# 09-Switch_Power_Filters.net
KiCad netlist of a schematic drawn in Altium Designer
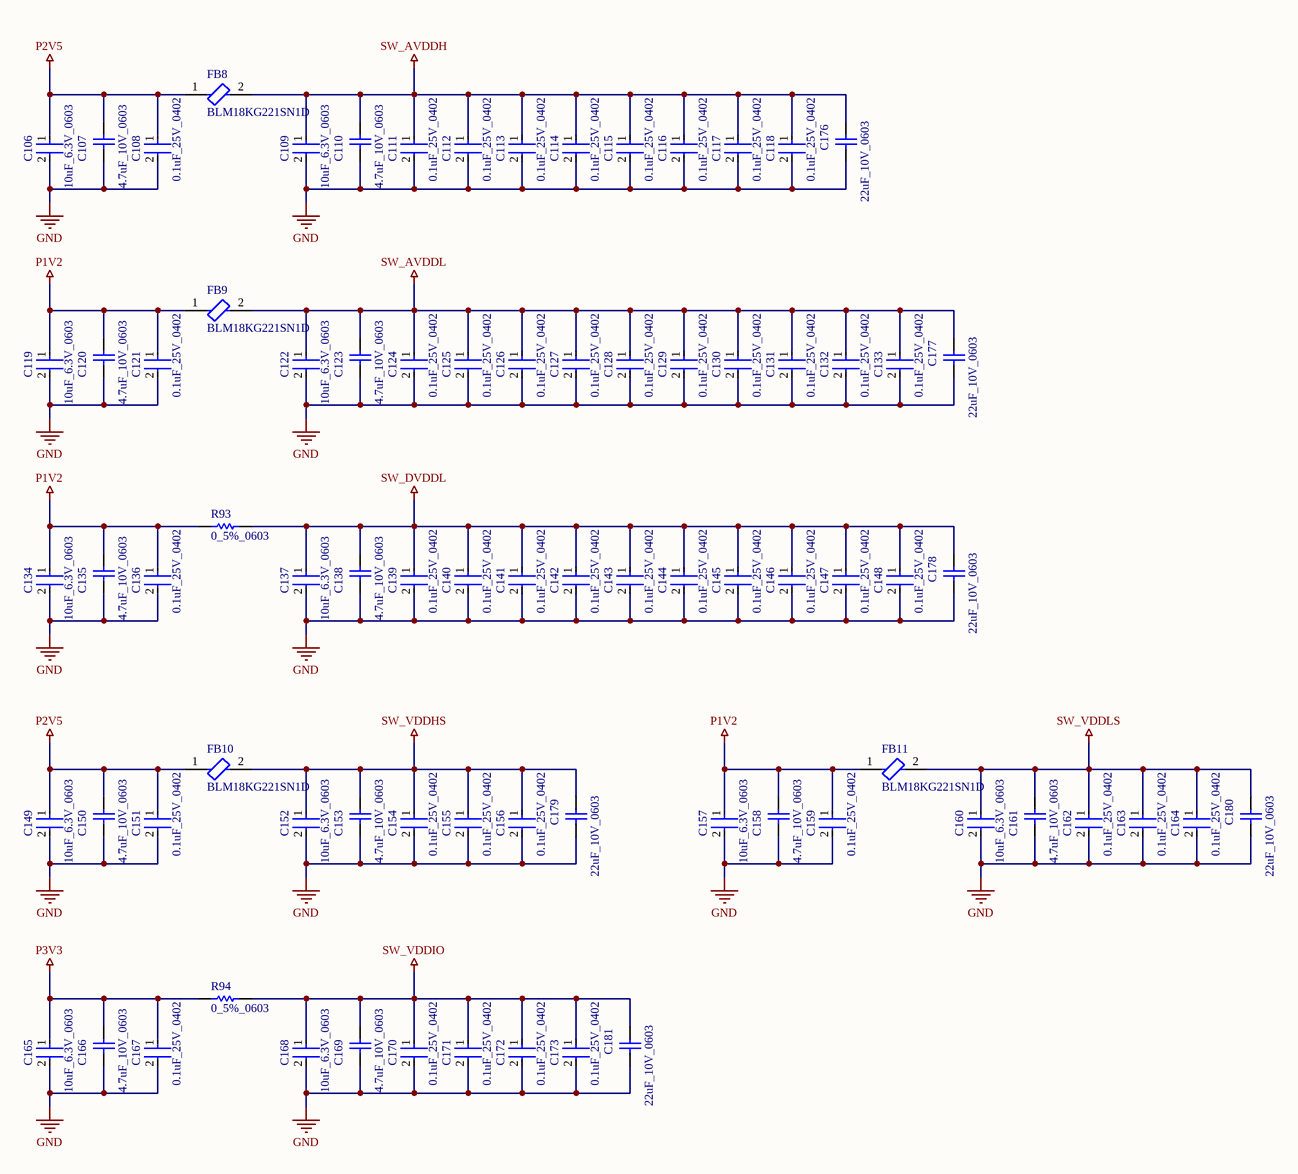
[diagram p0: 09-Switch_Power_Filters.SchDoc]

(export (version "E")
  (design (tool "Eeschema 10.0.6"))
  (components
    (comp (ref "C106")
      (value "10uF_6.3V_0603")
      (footprint "FP-C0603C106M9PACTU-MFG")
      (description "CAP CER 10UF 6.3V X5R 0603")
      (fields
        (field (name "MANUFACTURER PART NUMBER") "C0603C106M9PACTU")
        (field (name "MANUFACTURER") "Kemet")
      )
      (libsource (lib "Altium Content Vault") (part "b4654b650e69147ec39a6b967a45e02"))
    )
    (comp (ref "C107")
      (value "4.7uF_10V_0603")
      (footprint "CAPC1608X87X35NL15T15")
      (fields (field (name "PART NUMBER") "C0603C475K8PACTU") (field (name "MANUFACTURER") "Kemet"))
      (libsource (lib "Altium Content Vault") (part "CAP"))
    )
    (comp (ref "C108")
      (value "0.1uF_25V_0402")
      (footprint "FP-0402-L_1_0_1-W_0_5_0_1-IPC_C")
      (description "General Purpose Ceramic Capacitor, 0402, 100nF, 10%, X7R, 15%, 25V")
      (fields (field (name "VOLTAGE") "25V") (field (name "TOLERANCE") "10%"))
      (libsource (lib "Altium Content Vault") (part "b4654b650e69147ec39a6b967a45e02"))
    )
    (comp (ref "C109")
      (value "10uF_6.3V_0603")
      (footprint "FP-C0603C106M9PACTU-MFG")
      (description "CAP CER 10UF 6.3V X5R 0603")
      (fields
        (field (name "MANUFACTURER PART NUMBER") "C0603C106M9PACTU")
        (field (name "MANUFACTURER") "Kemet")
      )
      (libsource (lib "Altium Content Vault") (part "b4654b650e69147ec39a6b967a45e02"))
    )
    (comp (ref "C110")
      (value "4.7uF_10V_0603")
      (footprint "CAPC1608X87X35NL15T15")
      (fields (field (name "PART NUMBER") "C0603C475K8PACTU") (field (name "MANUFACTURER") "Kemet"))
      (libsource (lib "Altium Content Vault") (part "CAP"))
    )
    (comp (ref "C111")
      (value "0.1uF_25V_0402")
      (footprint "FP-0402-L_1_0_1-W_0_5_0_1-IPC_C")
      (description "General Purpose Ceramic Capacitor, 0402, 100nF, 10%, X7R, 15%, 25V")
      (fields (field (name "VOLTAGE") "25V") (field (name "TOLERANCE") "10%"))
      (libsource (lib "Altium Content Vault") (part "b4654b650e69147ec39a6b967a45e02"))
    )
    (comp (ref "C112")
      (value "0.1uF_25V_0402")
      (footprint "FP-0402-L_1_0_1-W_0_5_0_1-IPC_C")
      (description "General Purpose Ceramic Capacitor, 0402, 100nF, 10%, X7R, 15%, 25V")
      (fields (field (name "VOLTAGE") "25V") (field (name "TOLERANCE") "10%"))
      (libsource (lib "Altium Content Vault") (part "b4654b650e69147ec39a6b967a45e02"))
    )
    (comp (ref "C113")
      (value "0.1uF_25V_0402")
      (footprint "FP-0402-L_1_0_1-W_0_5_0_1-IPC_C")
      (description "General Purpose Ceramic Capacitor, 0402, 100nF, 10%, X7R, 15%, 25V")
      (fields (field (name "VOLTAGE") "25V") (field (name "TOLERANCE") "10%"))
      (libsource (lib "Altium Content Vault") (part "b4654b650e69147ec39a6b967a45e02"))
    )
    (comp (ref "C114")
      (value "0.1uF_25V_0402")
      (footprint "FP-0402-L_1_0_1-W_0_5_0_1-IPC_C")
      (description "General Purpose Ceramic Capacitor, 0402, 100nF, 10%, X7R, 15%, 25V")
      (fields (field (name "VOLTAGE") "25V") (field (name "TOLERANCE") "10%"))
      (libsource (lib "Altium Content Vault") (part "b4654b650e69147ec39a6b967a45e02"))
    )
    (comp (ref "C115")
      (value "0.1uF_25V_0402")
      (footprint "FP-0402-L_1_0_1-W_0_5_0_1-IPC_C")
      (description "General Purpose Ceramic Capacitor, 0402, 100nF, 10%, X7R, 15%, 25V")
      (fields (field (name "VOLTAGE") "25V") (field (name "TOLERANCE") "10%"))
      (libsource (lib "Altium Content Vault") (part "b4654b650e69147ec39a6b967a45e02"))
    )
    (comp (ref "C116")
      (value "0.1uF_25V_0402")
      (footprint "FP-0402-L_1_0_1-W_0_5_0_1-IPC_C")
      (description "General Purpose Ceramic Capacitor, 0402, 100nF, 10%, X7R, 15%, 25V")
      (fields (field (name "VOLTAGE") "25V") (field (name "TOLERANCE") "10%"))
      (libsource (lib "Altium Content Vault") (part "b4654b650e69147ec39a6b967a45e02"))
    )
    (comp (ref "C117")
      (value "0.1uF_25V_0402")
      (footprint "FP-0402-L_1_0_1-W_0_5_0_1-IPC_C")
      (description "General Purpose Ceramic Capacitor, 0402, 100nF, 10%, X7R, 15%, 25V")
      (fields (field (name "VOLTAGE") "25V") (field (name "TOLERANCE") "10%"))
      (libsource (lib "Altium Content Vault") (part "b4654b650e69147ec39a6b967a45e02"))
    )
    (comp (ref "C118")
      (value "0.1uF_25V_0402")
      (footprint "FP-0402-L_1_0_1-W_0_5_0_1-IPC_C")
      (description "General Purpose Ceramic Capacitor, 0402, 100nF, 10%, X7R, 15%, 25V")
      (fields (field (name "VOLTAGE") "25V") (field (name "TOLERANCE") "10%"))
      (libsource (lib "Altium Content Vault") (part "b4654b650e69147ec39a6b967a45e02"))
    )
    (comp (ref "C119")
      (value "10uF_6.3V_0603")
      (footprint "FP-C0603C106M9PACTU-MFG")
      (description "CAP CER 10UF 6.3V X5R 0603")
      (fields
        (field (name "MANUFACTURER PART NUMBER") "C0603C106M9PACTU")
        (field (name "MANUFACTURER") "Kemet")
      )
      (libsource (lib "Altium Content Vault") (part "b4654b650e69147ec39a6b967a45e02"))
    )
    (comp (ref "C120")
      (value "4.7uF_10V_0603")
      (footprint "CAPC1608X87X35NL15T15")
      (fields (field (name "PART NUMBER") "C0603C475K8PACTU") (field (name "MANUFACTURER") "Kemet"))
      (libsource (lib "Altium Content Vault") (part "CAP"))
    )
    (comp (ref "C121")
      (value "0.1uF_25V_0402")
      (footprint "FP-0402-L_1_0_1-W_0_5_0_1-IPC_C")
      (description "General Purpose Ceramic Capacitor, 0402, 100nF, 10%, X7R, 15%, 25V")
      (fields (field (name "VOLTAGE") "25V") (field (name "TOLERANCE") "10%"))
      (libsource (lib "Altium Content Vault") (part "b4654b650e69147ec39a6b967a45e02"))
    )
    (comp (ref "C122")
      (value "10uF_6.3V_0603")
      (footprint "FP-C0603C106M9PACTU-MFG")
      (description "CAP CER 10UF 6.3V X5R 0603")
      (fields
        (field (name "MANUFACTURER PART NUMBER") "C0603C106M9PACTU")
        (field (name "MANUFACTURER") "Kemet")
      )
      (libsource (lib "Altium Content Vault") (part "b4654b650e69147ec39a6b967a45e02"))
    )
    (comp (ref "C123")
      (value "4.7uF_10V_0603")
      (footprint "CAPC1608X87X35NL15T15")
      (fields (field (name "PART NUMBER") "C0603C475K8PACTU") (field (name "MANUFACTURER") "Kemet"))
      (libsource (lib "Altium Content Vault") (part "CAP"))
    )
    (comp (ref "C124")
      (value "0.1uF_25V_0402")
      (footprint "FP-0402-L_1_0_1-W_0_5_0_1-IPC_C")
      (description "General Purpose Ceramic Capacitor, 0402, 100nF, 10%, X7R, 15%, 25V")
      (fields (field (name "VOLTAGE") "25V") (field (name "TOLERANCE") "10%"))
      (libsource (lib "Altium Content Vault") (part "b4654b650e69147ec39a6b967a45e02"))
    )
    (comp (ref "C125")
      (value "0.1uF_25V_0402")
      (footprint "FP-0402-L_1_0_1-W_0_5_0_1-IPC_C")
      (description "General Purpose Ceramic Capacitor, 0402, 100nF, 10%, X7R, 15%, 25V")
      (fields (field (name "VOLTAGE") "25V") (field (name "TOLERANCE") "10%"))
      (libsource (lib "Altium Content Vault") (part "b4654b650e69147ec39a6b967a45e02"))
    )
    (comp (ref "C126")
      (value "0.1uF_25V_0402")
      (footprint "FP-0402-L_1_0_1-W_0_5_0_1-IPC_C")
      (description "General Purpose Ceramic Capacitor, 0402, 100nF, 10%, X7R, 15%, 25V")
      (fields (field (name "VOLTAGE") "25V") (field (name "TOLERANCE") "10%"))
      (libsource (lib "Altium Content Vault") (part "b4654b650e69147ec39a6b967a45e02"))
    )
    (comp (ref "C127")
      (value "0.1uF_25V_0402")
      (footprint "FP-0402-L_1_0_1-W_0_5_0_1-IPC_C")
      (description "General Purpose Ceramic Capacitor, 0402, 100nF, 10%, X7R, 15%, 25V")
      (fields (field (name "VOLTAGE") "25V") (field (name "TOLERANCE") "10%"))
      (libsource (lib "Altium Content Vault") (part "b4654b650e69147ec39a6b967a45e02"))
    )
    (comp (ref "C128")
      (value "0.1uF_25V_0402")
      (footprint "FP-0402-L_1_0_1-W_0_5_0_1-IPC_C")
      (description "General Purpose Ceramic Capacitor, 0402, 100nF, 10%, X7R, 15%, 25V")
      (fields (field (name "VOLTAGE") "25V") (field (name "TOLERANCE") "10%"))
      (libsource (lib "Altium Content Vault") (part "b4654b650e69147ec39a6b967a45e02"))
    )
    (comp (ref "C129")
      (value "0.1uF_25V_0402")
      (footprint "FP-0402-L_1_0_1-W_0_5_0_1-IPC_C")
      (description "General Purpose Ceramic Capacitor, 0402, 100nF, 10%, X7R, 15%, 25V")
      (fields (field (name "VOLTAGE") "25V") (field (name "TOLERANCE") "10%"))
      (libsource (lib "Altium Content Vault") (part "b4654b650e69147ec39a6b967a45e02"))
    )
    (comp (ref "C130")
      (value "0.1uF_25V_0402")
      (footprint "FP-0402-L_1_0_1-W_0_5_0_1-IPC_C")
      (description "General Purpose Ceramic Capacitor, 0402, 100nF, 10%, X7R, 15%, 25V")
      (fields (field (name "VOLTAGE") "25V") (field (name "TOLERANCE") "10%"))
      (libsource (lib "Altium Content Vault") (part "b4654b650e69147ec39a6b967a45e02"))
    )
    (comp (ref "C131")
      (value "0.1uF_25V_0402")
      (footprint "FP-0402-L_1_0_1-W_0_5_0_1-IPC_C")
      (description "General Purpose Ceramic Capacitor, 0402, 100nF, 10%, X7R, 15%, 25V")
      (fields (field (name "VOLTAGE") "25V") (field (name "TOLERANCE") "10%"))
      (libsource (lib "Altium Content Vault") (part "b4654b650e69147ec39a6b967a45e02"))
    )
    (comp (ref "C132")
      (value "0.1uF_25V_0402")
      (footprint "FP-0402-L_1_0_1-W_0_5_0_1-IPC_C")
      (description "General Purpose Ceramic Capacitor, 0402, 100nF, 10%, X7R, 15%, 25V")
      (fields (field (name "VOLTAGE") "25V") (field (name "TOLERANCE") "10%"))
      (libsource (lib "Altium Content Vault") (part "b4654b650e69147ec39a6b967a45e02"))
    )
    (comp (ref "C133")
      (value "0.1uF_25V_0402")
      (footprint "FP-0402-L_1_0_1-W_0_5_0_1-IPC_C")
      (description "General Purpose Ceramic Capacitor, 0402, 100nF, 10%, X7R, 15%, 25V")
      (fields (field (name "VOLTAGE") "25V") (field (name "TOLERANCE") "10%"))
      (libsource (lib "Altium Content Vault") (part "b4654b650e69147ec39a6b967a45e02"))
    )
    (comp (ref "C134")
      (value "10uF_6.3V_0603")
      (footprint "FP-C0603C106M9PACTU-MFG")
      (description "CAP CER 10UF 6.3V X5R 0603")
      (fields
        (field (name "MANUFACTURER PART NUMBER") "C0603C106M9PACTU")
        (field (name "MANUFACTURER") "Kemet")
      )
      (libsource (lib "Altium Content Vault") (part "b4654b650e69147ec39a6b967a45e02"))
    )
    (comp (ref "C135")
      (value "4.7uF_10V_0603")
      (footprint "CAPC1608X87X35NL15T15")
      (fields (field (name "PART NUMBER") "C0603C475K8PACTU") (field (name "MANUFACTURER") "Kemet"))
      (libsource (lib "Altium Content Vault") (part "CAP"))
    )
    (comp (ref "C136")
      (value "0.1uF_25V_0402")
      (footprint "FP-0402-L_1_0_1-W_0_5_0_1-IPC_C")
      (description "General Purpose Ceramic Capacitor, 0402, 100nF, 10%, X7R, 15%, 25V")
      (fields (field (name "VOLTAGE") "25V") (field (name "TOLERANCE") "10%"))
      (libsource (lib "Altium Content Vault") (part "b4654b650e69147ec39a6b967a45e02"))
    )
    (comp (ref "C137")
      (value "10uF_6.3V_0603")
      (footprint "FP-C0603C106M9PACTU-MFG")
      (description "CAP CER 10UF 6.3V X5R 0603")
      (fields
        (field (name "MANUFACTURER PART NUMBER") "C0603C106M9PACTU")
        (field (name "MANUFACTURER") "Kemet")
      )
      (libsource (lib "Altium Content Vault") (part "b4654b650e69147ec39a6b967a45e02"))
    )
    (comp (ref "C138")
      (value "4.7uF_10V_0603")
      (footprint "CAPC1608X87X35NL15T15")
      (fields (field (name "PART NUMBER") "C0603C475K8PACTU") (field (name "MANUFACTURER") "Kemet"))
      (libsource (lib "Altium Content Vault") (part "CAP"))
    )
    (comp (ref "C139")
      (value "0.1uF_25V_0402")
      (footprint "FP-0402-L_1_0_1-W_0_5_0_1-IPC_C")
      (description "General Purpose Ceramic Capacitor, 0402, 100nF, 10%, X7R, 15%, 25V")
      (fields (field (name "VOLTAGE") "25V") (field (name "TOLERANCE") "10%"))
      (libsource (lib "Altium Content Vault") (part "b4654b650e69147ec39a6b967a45e02"))
    )
    (comp (ref "C140")
      (value "0.1uF_25V_0402")
      (footprint "FP-0402-L_1_0_1-W_0_5_0_1-IPC_C")
      (description "General Purpose Ceramic Capacitor, 0402, 100nF, 10%, X7R, 15%, 25V")
      (fields (field (name "VOLTAGE") "25V") (field (name "TOLERANCE") "10%"))
      (libsource (lib "Altium Content Vault") (part "b4654b650e69147ec39a6b967a45e02"))
    )
    (comp (ref "C141")
      (value "0.1uF_25V_0402")
      (footprint "FP-0402-L_1_0_1-W_0_5_0_1-IPC_C")
      (description "General Purpose Ceramic Capacitor, 0402, 100nF, 10%, X7R, 15%, 25V")
      (fields (field (name "VOLTAGE") "25V") (field (name "TOLERANCE") "10%"))
      (libsource (lib "Altium Content Vault") (part "b4654b650e69147ec39a6b967a45e02"))
    )
    (comp (ref "C142")
      (value "0.1uF_25V_0402")
      (footprint "FP-0402-L_1_0_1-W_0_5_0_1-IPC_C")
      (description "General Purpose Ceramic Capacitor, 0402, 100nF, 10%, X7R, 15%, 25V")
      (fields (field (name "VOLTAGE") "25V") (field (name "TOLERANCE") "10%"))
      (libsource (lib "Altium Content Vault") (part "b4654b650e69147ec39a6b967a45e02"))
    )
    (comp (ref "C143")
      (value "0.1uF_25V_0402")
      (footprint "FP-0402-L_1_0_1-W_0_5_0_1-IPC_C")
      (description "General Purpose Ceramic Capacitor, 0402, 100nF, 10%, X7R, 15%, 25V")
      (fields (field (name "VOLTAGE") "25V") (field (name "TOLERANCE") "10%"))
      (libsource (lib "Altium Content Vault") (part "b4654b650e69147ec39a6b967a45e02"))
    )
    (comp (ref "C144")
      (value "0.1uF_25V_0402")
      (footprint "FP-0402-L_1_0_1-W_0_5_0_1-IPC_C")
      (description "General Purpose Ceramic Capacitor, 0402, 100nF, 10%, X7R, 15%, 25V")
      (fields (field (name "VOLTAGE") "25V") (field (name "TOLERANCE") "10%"))
      (libsource (lib "Altium Content Vault") (part "b4654b650e69147ec39a6b967a45e02"))
    )
    (comp (ref "C145")
      (value "0.1uF_25V_0402")
      (footprint "FP-0402-L_1_0_1-W_0_5_0_1-IPC_C")
      (description "General Purpose Ceramic Capacitor, 0402, 100nF, 10%, X7R, 15%, 25V")
      (fields (field (name "VOLTAGE") "25V") (field (name "TOLERANCE") "10%"))
      (libsource (lib "Altium Content Vault") (part "b4654b650e69147ec39a6b967a45e02"))
    )
    (comp (ref "C146")
      (value "0.1uF_25V_0402")
      (footprint "FP-0402-L_1_0_1-W_0_5_0_1-IPC_C")
      (description "General Purpose Ceramic Capacitor, 0402, 100nF, 10%, X7R, 15%, 25V")
      (fields (field (name "VOLTAGE") "25V") (field (name "TOLERANCE") "10%"))
      (libsource (lib "Altium Content Vault") (part "b4654b650e69147ec39a6b967a45e02"))
    )
    (comp (ref "C147")
      (value "0.1uF_25V_0402")
      (footprint "FP-0402-L_1_0_1-W_0_5_0_1-IPC_C")
      (description "General Purpose Ceramic Capacitor, 0402, 100nF, 10%, X7R, 15%, 25V")
      (fields (field (name "VOLTAGE") "25V") (field (name "TOLERANCE") "10%"))
      (libsource (lib "Altium Content Vault") (part "b4654b650e69147ec39a6b967a45e02"))
    )
    (comp (ref "C148")
      (value "0.1uF_25V_0402")
      (footprint "FP-0402-L_1_0_1-W_0_5_0_1-IPC_C")
      (description "General Purpose Ceramic Capacitor, 0402, 100nF, 10%, X7R, 15%, 25V")
      (fields (field (name "VOLTAGE") "25V") (field (name "TOLERANCE") "10%"))
      (libsource (lib "Altium Content Vault") (part "b4654b650e69147ec39a6b967a45e02"))
    )
    (comp (ref "C149")
      (value "10uF_6.3V_0603")
      (footprint "FP-C0603C106M9PACTU-MFG")
      (description "CAP CER 10UF 6.3V X5R 0603")
      (fields
        (field (name "MANUFACTURER PART NUMBER") "C0603C106M9PACTU")
        (field (name "MANUFACTURER") "Kemet")
      )
      (libsource (lib "Altium Content Vault") (part "b4654b650e69147ec39a6b967a45e02"))
    )
    (comp (ref "C150")
      (value "4.7uF_10V_0603")
      (footprint "CAPC1608X87X35NL15T15")
      (fields (field (name "PART NUMBER") "C0603C475K8PACTU") (field (name "MANUFACTURER") "Kemet"))
      (libsource (lib "Altium Content Vault") (part "CAP"))
    )
    (comp (ref "C151")
      (value "0.1uF_25V_0402")
      (footprint "FP-0402-L_1_0_1-W_0_5_0_1-IPC_C")
      (description "General Purpose Ceramic Capacitor, 0402, 100nF, 10%, X7R, 15%, 25V")
      (fields (field (name "VOLTAGE") "25V") (field (name "TOLERANCE") "10%"))
      (libsource (lib "Altium Content Vault") (part "b4654b650e69147ec39a6b967a45e02"))
    )
    (comp (ref "C152")
      (value "10uF_6.3V_0603")
      (footprint "FP-C0603C106M9PACTU-MFG")
      (description "CAP CER 10UF 6.3V X5R 0603")
      (fields
        (field (name "MANUFACTURER PART NUMBER") "C0603C106M9PACTU")
        (field (name "MANUFACTURER") "Kemet")
      )
      (libsource (lib "Altium Content Vault") (part "b4654b650e69147ec39a6b967a45e02"))
    )
    (comp (ref "C153")
      (value "4.7uF_10V_0603")
      (footprint "CAPC1608X87X35NL15T15")
      (fields (field (name "PART NUMBER") "C0603C475K8PACTU") (field (name "MANUFACTURER") "Kemet"))
      (libsource (lib "Altium Content Vault") (part "CAP"))
    )
    (comp (ref "C154")
      (value "0.1uF_25V_0402")
      (footprint "FP-0402-L_1_0_1-W_0_5_0_1-IPC_C")
      (description "General Purpose Ceramic Capacitor, 0402, 100nF, 10%, X7R, 15%, 25V")
      (fields (field (name "VOLTAGE") "25V") (field (name "TOLERANCE") "10%"))
      (libsource (lib "Altium Content Vault") (part "b4654b650e69147ec39a6b967a45e02"))
    )
    (comp (ref "C155")
      (value "0.1uF_25V_0402")
      (footprint "FP-0402-L_1_0_1-W_0_5_0_1-IPC_C")
      (description "General Purpose Ceramic Capacitor, 0402, 100nF, 10%, X7R, 15%, 25V")
      (fields (field (name "VOLTAGE") "25V") (field (name "TOLERANCE") "10%"))
      (libsource (lib "Altium Content Vault") (part "b4654b650e69147ec39a6b967a45e02"))
    )
    (comp (ref "C156")
      (value "0.1uF_25V_0402")
      (footprint "FP-0402-L_1_0_1-W_0_5_0_1-IPC_C")
      (description "General Purpose Ceramic Capacitor, 0402, 100nF, 10%, X7R, 15%, 25V")
      (fields (field (name "VOLTAGE") "25V") (field (name "TOLERANCE") "10%"))
      (libsource (lib "Altium Content Vault") (part "b4654b650e69147ec39a6b967a45e02"))
    )
    (comp (ref "C157")
      (value "10uF_6.3V_0603")
      (footprint "FP-C0603C106M9PACTU-MFG")
      (description "CAP CER 10UF 6.3V X5R 0603")
      (fields
        (field (name "MANUFACTURER PART NUMBER") "C0603C106M9PACTU")
        (field (name "MANUFACTURER") "Kemet")
      )
      (libsource (lib "Altium Content Vault") (part "b4654b650e69147ec39a6b967a45e02"))
    )
    (comp (ref "C158")
      (value "4.7uF_10V_0603")
      (footprint "CAPC1608X87X35NL15T15")
      (fields (field (name "PART NUMBER") "C0603C475K8PACTU") (field (name "MANUFACTURER") "Kemet"))
      (libsource (lib "Altium Content Vault") (part "CAP"))
    )
    (comp (ref "C159")
      (value "0.1uF_25V_0402")
      (footprint "FP-0402-L_1_0_1-W_0_5_0_1-IPC_C")
      (description "General Purpose Ceramic Capacitor, 0402, 100nF, 10%, X7R, 15%, 25V")
      (fields (field (name "VOLTAGE") "25V") (field (name "TOLERANCE") "10%"))
      (libsource (lib "Altium Content Vault") (part "b4654b650e69147ec39a6b967a45e02"))
    )
    (comp (ref "C160")
      (value "10uF_6.3V_0603")
      (footprint "FP-C0603C106M9PACTU-MFG")
      (description "CAP CER 10UF 6.3V X5R 0603")
      (fields
        (field (name "MANUFACTURER PART NUMBER") "C0603C106M9PACTU")
        (field (name "MANUFACTURER") "Kemet")
      )
      (libsource (lib "Altium Content Vault") (part "b4654b650e69147ec39a6b967a45e02"))
    )
    (comp (ref "C161")
      (value "4.7uF_10V_0603")
      (footprint "CAPC1608X87X35NL15T15")
      (fields (field (name "PART NUMBER") "C0603C475K8PACTU") (field (name "MANUFACTURER") "Kemet"))
      (libsource (lib "Altium Content Vault") (part "CAP"))
    )
    (comp (ref "C162")
      (value "0.1uF_25V_0402")
      (footprint "FP-0402-L_1_0_1-W_0_5_0_1-IPC_C")
      (description "General Purpose Ceramic Capacitor, 0402, 100nF, 10%, X7R, 15%, 25V")
      (fields (field (name "VOLTAGE") "25V") (field (name "TOLERANCE") "10%"))
      (libsource (lib "Altium Content Vault") (part "b4654b650e69147ec39a6b967a45e02"))
    )
    (comp (ref "C163")
      (value "0.1uF_25V_0402")
      (footprint "FP-0402-L_1_0_1-W_0_5_0_1-IPC_C")
      (description "General Purpose Ceramic Capacitor, 0402, 100nF, 10%, X7R, 15%, 25V")
      (fields (field (name "VOLTAGE") "25V") (field (name "TOLERANCE") "10%"))
      (libsource (lib "Altium Content Vault") (part "b4654b650e69147ec39a6b967a45e02"))
    )
    (comp (ref "C164")
      (value "0.1uF_25V_0402")
      (footprint "FP-0402-L_1_0_1-W_0_5_0_1-IPC_C")
      (description "General Purpose Ceramic Capacitor, 0402, 100nF, 10%, X7R, 15%, 25V")
      (fields (field (name "VOLTAGE") "25V") (field (name "TOLERANCE") "10%"))
      (libsource (lib "Altium Content Vault") (part "b4654b650e69147ec39a6b967a45e02"))
    )
    (comp (ref "C165")
      (value "10uF_6.3V_0603")
      (footprint "FP-C0603C106M9PACTU-MFG")
      (description "CAP CER 10UF 6.3V X5R 0603")
      (fields
        (field (name "MANUFACTURER PART NUMBER") "C0603C106M9PACTU")
        (field (name "MANUFACTURER") "Kemet")
      )
      (libsource (lib "Altium Content Vault") (part "b4654b650e69147ec39a6b967a45e02"))
    )
    (comp (ref "C166")
      (value "4.7uF_10V_0603")
      (footprint "CAPC1608X87X35NL15T15")
      (fields (field (name "PART NUMBER") "C0603C475K8PACTU") (field (name "MANUFACTURER") "Kemet"))
      (libsource (lib "Altium Content Vault") (part "CAP"))
    )
    (comp (ref "C167")
      (value "0.1uF_25V_0402")
      (footprint "FP-0402-L_1_0_1-W_0_5_0_1-IPC_C")
      (description "General Purpose Ceramic Capacitor, 0402, 100nF, 10%, X7R, 15%, 25V")
      (fields (field (name "VOLTAGE") "25V") (field (name "TOLERANCE") "10%"))
      (libsource (lib "Altium Content Vault") (part "b4654b650e69147ec39a6b967a45e02"))
    )
    (comp (ref "C168")
      (value "10uF_6.3V_0603")
      (footprint "FP-C0603C106M9PACTU-MFG")
      (description "CAP CER 10UF 6.3V X5R 0603")
      (fields
        (field (name "MANUFACTURER PART NUMBER") "C0603C106M9PACTU")
        (field (name "MANUFACTURER") "Kemet")
      )
      (libsource (lib "Altium Content Vault") (part "b4654b650e69147ec39a6b967a45e02"))
    )
    (comp (ref "C169")
      (value "4.7uF_10V_0603")
      (footprint "CAPC1608X87X35NL15T15")
      (fields (field (name "PART NUMBER") "C0603C475K8PACTU") (field (name "MANUFACTURER") "Kemet"))
      (libsource (lib "Altium Content Vault") (part "CAP"))
    )
    (comp (ref "C170")
      (value "0.1uF_25V_0402")
      (footprint "FP-0402-L_1_0_1-W_0_5_0_1-IPC_C")
      (description "General Purpose Ceramic Capacitor, 0402, 100nF, 10%, X7R, 15%, 25V")
      (fields (field (name "VOLTAGE") "25V") (field (name "TOLERANCE") "10%"))
      (libsource (lib "Altium Content Vault") (part "b4654b650e69147ec39a6b967a45e02"))
    )
    (comp (ref "C171")
      (value "0.1uF_25V_0402")
      (footprint "FP-0402-L_1_0_1-W_0_5_0_1-IPC_C")
      (description "General Purpose Ceramic Capacitor, 0402, 100nF, 10%, X7R, 15%, 25V")
      (fields (field (name "VOLTAGE") "25V") (field (name "TOLERANCE") "10%"))
      (libsource (lib "Altium Content Vault") (part "b4654b650e69147ec39a6b967a45e02"))
    )
    (comp (ref "C172")
      (value "0.1uF_25V_0402")
      (footprint "FP-0402-L_1_0_1-W_0_5_0_1-IPC_C")
      (description "General Purpose Ceramic Capacitor, 0402, 100nF, 10%, X7R, 15%, 25V")
      (fields (field (name "VOLTAGE") "25V") (field (name "TOLERANCE") "10%"))
      (libsource (lib "Altium Content Vault") (part "b4654b650e69147ec39a6b967a45e02"))
    )
    (comp (ref "C173")
      (value "0.1uF_25V_0402")
      (footprint "FP-0402-L_1_0_1-W_0_5_0_1-IPC_C")
      (description "General Purpose Ceramic Capacitor, 0402, 100nF, 10%, X7R, 15%, 25V")
      (fields (field (name "VOLTAGE") "25V") (field (name "TOLERANCE") "10%"))
      (libsource (lib "Altium Content Vault") (part "b4654b650e69147ec39a6b967a45e02"))
    )
    (comp (ref "C176")
      (value "22uF_10V_0603")
      (footprint "CAPC1608X100X20ML10")
      (description "Chip Capacitor, 22 uF, +/- 20%, 10 V, -55 to 85 degC, 0603 (1608 Metric), RoHS, Tape and Reel")
      (fields (field (name "MANUFACTURER") "TDK") (field (name "TOLERANCE") "±20%"))
      (libsource (lib "Altium Content Vault") (part "CAP-NP-2"))
    )
    (comp (ref "C177")
      (value "22uF_10V_0603")
      (footprint "CAPC1608X100X20ML10")
      (description "Chip Capacitor, 22 uF, +/- 20%, 10 V, -55 to 85 degC, 0603 (1608 Metric), RoHS, Tape and Reel")
      (fields (field (name "MANUFACTURER") "TDK") (field (name "TOLERANCE") "±20%"))
      (libsource (lib "Altium Content Vault") (part "CAP-NP-2"))
    )
    (comp (ref "C178")
      (value "22uF_10V_0603")
      (footprint "CAPC1608X100X20ML10")
      (description "Chip Capacitor, 22 uF, +/- 20%, 10 V, -55 to 85 degC, 0603 (1608 Metric), RoHS, Tape and Reel")
      (fields (field (name "MANUFACTURER") "TDK") (field (name "TOLERANCE") "±20%"))
      (libsource (lib "Altium Content Vault") (part "CAP-NP-2"))
    )
    (comp (ref "C179")
      (value "22uF_10V_0603")
      (footprint "CAPC1608X100X20ML10")
      (description "Chip Capacitor, 22 uF, +/- 20%, 10 V, -55 to 85 degC, 0603 (1608 Metric), RoHS, Tape and Reel")
      (fields (field (name "MANUFACTURER") "TDK") (field (name "TOLERANCE") "±20%"))
      (libsource (lib "Altium Content Vault") (part "CAP-NP-2"))
    )
    (comp (ref "C180")
      (value "22uF_10V_0603")
      (footprint "CAPC1608X100X20ML10")
      (description "Chip Capacitor, 22 uF, +/- 20%, 10 V, -55 to 85 degC, 0603 (1608 Metric), RoHS, Tape and Reel")
      (fields (field (name "MANUFACTURER") "TDK") (field (name "TOLERANCE") "±20%"))
      (libsource (lib "Altium Content Vault") (part "CAP-NP-2"))
    )
    (comp (ref "C181")
      (value "22uF_10V_0603")
      (footprint "CAPC1608X100X20ML10")
      (description "Chip Capacitor, 22 uF, +/- 20%, 10 V, -55 to 85 degC, 0603 (1608 Metric), RoHS, Tape and Reel")
      (fields (field (name "MANUFACTURER") "TDK") (field (name "TOLERANCE") "±20%"))
      (libsource (lib "Altium Content Vault") (part "CAP-NP-2"))
    )
    (comp (ref "FB8")
      (value "BLM18KG221SN1D")
      (footprint "FP-BLM18-0_15-t0_8-IPC_B")
      (description "Chip Ferrite Bead, 0603, 220Ω @ 100MHz, 0.05Ω, 25%, 2.2A")
      (fields (field (name "TOLERANCE") "25%"))
      (libsource (lib "Altium Content Vault") (part "5f30dd21d616792df468990f7003faa"))
    )
    (comp (ref "FB9")
      (value "BLM18KG221SN1D")
      (footprint "FP-BLM18-0_15-t0_8-IPC_B")
      (description "Chip Ferrite Bead, 0603, 220Ω @ 100MHz, 0.05Ω, 25%, 2.2A")
      (fields (field (name "TOLERANCE") "25%"))
      (libsource (lib "Altium Content Vault") (part "5f30dd21d616792df468990f7003faa"))
    )
    (comp (ref "FB10")
      (value "BLM18KG221SN1D")
      (footprint "FP-BLM18-0_15-t0_8-IPC_B")
      (description "Chip Ferrite Bead, 0603, 220Ω @ 100MHz, 0.05Ω, 25%, 2.2A")
      (fields (field (name "TOLERANCE") "25%"))
      (libsource (lib "Altium Content Vault") (part "5f30dd21d616792df468990f7003faa"))
    )
    (comp (ref "FB11")
      (value "BLM18KG221SN1D")
      (footprint "FP-BLM18-0_15-t0_8-IPC_B")
      (description "Chip Ferrite Bead, 0603, 220Ω @ 100MHz, 0.05Ω, 25%, 2.2A")
      (fields (field (name "TOLERANCE") "25%"))
      (libsource (lib "Altium Content Vault") (part "5f30dd21d616792df468990f7003faa"))
    )
    (comp (ref "R93")
      (value "0_5%_0603")
      (footprint "RESC1608X55X25ML10T15")
      (description "Chip Resistor, 0 Ohm, +/- 5%, 0.1 W, -55 to 155 degC, 0603 (1608 Metric), RoHS, Tape and Reel")
      (fields (field (name "TOLERANCE") "5%") (field (name "MANUFACTURER") "Yageo"))
      (libsource (lib "Altium Content Vault") (part "RES-2"))
    )
    (comp (ref "R94")
      (value "0_5%_0603")
      (footprint "RESC1608X55X25ML10T15")
      (description "Chip Resistor, 0 Ohm, +/- 5%, 0.1 W, -55 to 155 degC, 0603 (1608 Metric), RoHS, Tape and Reel")
      (fields (field (name "TOLERANCE") "5%") (field (name "MANUFACTURER") "Yageo"))
      (libsource (lib "Altium Content Vault") (part "RES-2"))
    )
  )
  (nets
    (net (code "1") (name "GND") (class "Default")
      (node (ref "C106") (pin "2") (pinfunction "2_2") (pintype "passive"))
      (node (ref "C107") (pin "1") (pinfunction "1_1") (pintype "passive"))
      (node (ref "C108") (pin "2") (pinfunction "2_2") (pintype "passive"))
      (node (ref "C109") (pin "2") (pinfunction "2_2") (pintype "passive"))
      (node (ref "C110") (pin "1") (pinfunction "1_1") (pintype "passive"))
      (node (ref "C111") (pin "2") (pinfunction "2_2") (pintype "passive"))
      (node (ref "C112") (pin "2") (pinfunction "2_2") (pintype "passive"))
      (node (ref "C113") (pin "2") (pinfunction "2_2") (pintype "passive"))
      (node (ref "C114") (pin "2") (pinfunction "2_2") (pintype "passive"))
      (node (ref "C115") (pin "2") (pinfunction "2_2") (pintype "passive"))
      (node (ref "C116") (pin "2") (pinfunction "2_2") (pintype "passive"))
      (node (ref "C117") (pin "2") (pinfunction "2_2") (pintype "passive"))
      (node (ref "C118") (pin "2") (pinfunction "2_2") (pintype "passive"))
      (node (ref "C119") (pin "2") (pinfunction "2_2") (pintype "passive"))
      (node (ref "C120") (pin "1") (pinfunction "1_1") (pintype "passive"))
      (node (ref "C121") (pin "2") (pinfunction "2_2") (pintype "passive"))
      (node (ref "C122") (pin "2") (pinfunction "2_2") (pintype "passive"))
      (node (ref "C123") (pin "1") (pinfunction "1_1") (pintype "passive"))
      (node (ref "C124") (pin "2") (pinfunction "2_2") (pintype "passive"))
      (node (ref "C125") (pin "2") (pinfunction "2_2") (pintype "passive"))
      (node (ref "C126") (pin "2") (pinfunction "2_2") (pintype "passive"))
      (node (ref "C127") (pin "2") (pinfunction "2_2") (pintype "passive"))
      (node (ref "C128") (pin "2") (pinfunction "2_2") (pintype "passive"))
      (node (ref "C129") (pin "2") (pinfunction "2_2") (pintype "passive"))
      (node (ref "C130") (pin "2") (pinfunction "2_2") (pintype "passive"))
      (node (ref "C131") (pin "2") (pinfunction "2_2") (pintype "passive"))
      (node (ref "C132") (pin "2") (pinfunction "2_2") (pintype "passive"))
      (node (ref "C133") (pin "2") (pinfunction "2_2") (pintype "passive"))
      (node (ref "C134") (pin "2") (pinfunction "2_2") (pintype "passive"))
      (node (ref "C135") (pin "1") (pinfunction "1_1") (pintype "passive"))
      (node (ref "C136") (pin "2") (pinfunction "2_2") (pintype "passive"))
      (node (ref "C137") (pin "2") (pinfunction "2_2") (pintype "passive"))
      (node (ref "C138") (pin "1") (pinfunction "1_1") (pintype "passive"))
      (node (ref "C139") (pin "2") (pinfunction "2_2") (pintype "passive"))
      (node (ref "C140") (pin "2") (pinfunction "2_2") (pintype "passive"))
      (node (ref "C141") (pin "2") (pinfunction "2_2") (pintype "passive"))
      (node (ref "C142") (pin "2") (pinfunction "2_2") (pintype "passive"))
      (node (ref "C143") (pin "2") (pinfunction "2_2") (pintype "passive"))
      (node (ref "C144") (pin "2") (pinfunction "2_2") (pintype "passive"))
      (node (ref "C145") (pin "2") (pinfunction "2_2") (pintype "passive"))
      (node (ref "C146") (pin "2") (pinfunction "2_2") (pintype "passive"))
      (node (ref "C147") (pin "2") (pinfunction "2_2") (pintype "passive"))
      (node (ref "C148") (pin "2") (pinfunction "2_2") (pintype "passive"))
      (node (ref "C149") (pin "2") (pinfunction "2_2") (pintype "passive"))
      (node (ref "C150") (pin "1") (pinfunction "1_1") (pintype "passive"))
      (node (ref "C151") (pin "2") (pinfunction "2_2") (pintype "passive"))
      (node (ref "C152") (pin "2") (pinfunction "2_2") (pintype "passive"))
      (node (ref "C153") (pin "1") (pinfunction "1_1") (pintype "passive"))
      (node (ref "C154") (pin "2") (pinfunction "2_2") (pintype "passive"))
      (node (ref "C155") (pin "2") (pinfunction "2_2") (pintype "passive"))
      (node (ref "C156") (pin "2") (pinfunction "2_2") (pintype "passive"))
      (node (ref "C157") (pin "2") (pinfunction "2_2") (pintype "passive"))
      (node (ref "C158") (pin "1") (pinfunction "1_1") (pintype "passive"))
      (node (ref "C159") (pin "2") (pinfunction "2_2") (pintype "passive"))
      (node (ref "C160") (pin "2") (pinfunction "2_2") (pintype "passive"))
      (node (ref "C161") (pin "1") (pinfunction "1_1") (pintype "passive"))
      (node (ref "C162") (pin "2") (pinfunction "2_2") (pintype "passive"))
      (node (ref "C163") (pin "2") (pinfunction "2_2") (pintype "passive"))
      (node (ref "C164") (pin "2") (pinfunction "2_2") (pintype "passive"))
      (node (ref "C165") (pin "2") (pinfunction "2_2") (pintype "passive"))
      (node (ref "C166") (pin "1") (pinfunction "1_1") (pintype "passive"))
      (node (ref "C167") (pin "2") (pinfunction "2_2") (pintype "passive"))
      (node (ref "C168") (pin "2") (pinfunction "2_2") (pintype "passive"))
      (node (ref "C169") (pin "1") (pinfunction "1_1") (pintype "passive"))
      (node (ref "C170") (pin "2") (pinfunction "2_2") (pintype "passive"))
      (node (ref "C171") (pin "2") (pinfunction "2_2") (pintype "passive"))
      (node (ref "C172") (pin "2") (pinfunction "2_2") (pintype "passive"))
      (node (ref "C173") (pin "2") (pinfunction "2_2") (pintype "passive"))
      (node (ref "C176") (pin "1") (pinfunction "1_1") (pintype "passive"))
      (node (ref "C177") (pin "1") (pinfunction "1_1") (pintype "passive"))
      (node (ref "C178") (pin "1") (pinfunction "1_1") (pintype "passive"))
      (node (ref "C179") (pin "1") (pinfunction "1_1") (pintype "passive"))
      (node (ref "C180") (pin "1") (pinfunction "1_1") (pintype "passive"))
      (node (ref "C181") (pin "1") (pinfunction "1_1") (pintype "passive"))
    )
    (net (code "2") (name "P1V2") (class "Default")
      (node (ref "C119") (pin "1") (pinfunction "1_1") (pintype "passive"))
      (node (ref "C120") (pin "2") (pinfunction "2_2") (pintype "passive"))
      (node (ref "C121") (pin "1") (pinfunction "1_1") (pintype "passive"))
      (node (ref "C134") (pin "1") (pinfunction "1_1") (pintype "passive"))
      (node (ref "C135") (pin "2") (pinfunction "2_2") (pintype "passive"))
      (node (ref "C136") (pin "1") (pinfunction "1_1") (pintype "passive"))
      (node (ref "C157") (pin "1") (pinfunction "1_1") (pintype "passive"))
      (node (ref "C158") (pin "2") (pinfunction "2_2") (pintype "passive"))
      (node (ref "C159") (pin "1") (pinfunction "1_1") (pintype "passive"))
      (node (ref "FB11") (pin "1") (pinfunction "1_1") (pintype "passive"))
      (node (ref "FB9") (pin "1") (pinfunction "1_1") (pintype "passive"))
      (node (ref "R93") (pin "1") (pinfunction "1_1") (pintype "passive"))
    )
    (net (code "3") (name "P2V5") (class "Default")
      (node (ref "C106") (pin "1") (pinfunction "1_1") (pintype "passive"))
      (node (ref "C107") (pin "2") (pinfunction "2_2") (pintype "passive"))
      (node (ref "C108") (pin "1") (pinfunction "1_1") (pintype "passive"))
      (node (ref "C149") (pin "1") (pinfunction "1_1") (pintype "passive"))
      (node (ref "C150") (pin "2") (pinfunction "2_2") (pintype "passive"))
      (node (ref "C151") (pin "1") (pinfunction "1_1") (pintype "passive"))
      (node (ref "FB10") (pin "1") (pinfunction "1_1") (pintype "passive"))
      (node (ref "FB8") (pin "1") (pinfunction "1_1") (pintype "passive"))
    )
    (net (code "4") (name "P3V3") (class "Default")
      (node (ref "C165") (pin "1") (pinfunction "1_1") (pintype "passive"))
      (node (ref "C166") (pin "2") (pinfunction "2_2") (pintype "passive"))
      (node (ref "C167") (pin "1") (pinfunction "1_1") (pintype "passive"))
      (node (ref "R94") (pin "1") (pinfunction "1_1") (pintype "passive"))
    )
    (net (code "5") (name "SW_AVDDH") (class "Default")
      (node (ref "C109") (pin "1") (pinfunction "1_1") (pintype "passive"))
      (node (ref "C110") (pin "2") (pinfunction "2_2") (pintype "passive"))
      (node (ref "C111") (pin "1") (pinfunction "1_1") (pintype "passive"))
      (node (ref "C112") (pin "1") (pinfunction "1_1") (pintype "passive"))
      (node (ref "C113") (pin "1") (pinfunction "1_1") (pintype "passive"))
      (node (ref "C114") (pin "1") (pinfunction "1_1") (pintype "passive"))
      (node (ref "C115") (pin "1") (pinfunction "1_1") (pintype "passive"))
      (node (ref "C116") (pin "1") (pinfunction "1_1") (pintype "passive"))
      (node (ref "C117") (pin "1") (pinfunction "1_1") (pintype "passive"))
      (node (ref "C118") (pin "1") (pinfunction "1_1") (pintype "passive"))
      (node (ref "C176") (pin "2") (pinfunction "2_2") (pintype "passive"))
      (node (ref "FB8") (pin "2") (pinfunction "2_2") (pintype "passive"))
    )
    (net (code "6") (name "SW_AVDDL") (class "Default")
      (node (ref "C122") (pin "1") (pinfunction "1_1") (pintype "passive"))
      (node (ref "C123") (pin "2") (pinfunction "2_2") (pintype "passive"))
      (node (ref "C124") (pin "1") (pinfunction "1_1") (pintype "passive"))
      (node (ref "C125") (pin "1") (pinfunction "1_1") (pintype "passive"))
      (node (ref "C126") (pin "1") (pinfunction "1_1") (pintype "passive"))
      (node (ref "C127") (pin "1") (pinfunction "1_1") (pintype "passive"))
      (node (ref "C128") (pin "1") (pinfunction "1_1") (pintype "passive"))
      (node (ref "C129") (pin "1") (pinfunction "1_1") (pintype "passive"))
      (node (ref "C130") (pin "1") (pinfunction "1_1") (pintype "passive"))
      (node (ref "C131") (pin "1") (pinfunction "1_1") (pintype "passive"))
      (node (ref "C132") (pin "1") (pinfunction "1_1") (pintype "passive"))
      (node (ref "C133") (pin "1") (pinfunction "1_1") (pintype "passive"))
      (node (ref "C177") (pin "2") (pinfunction "2_2") (pintype "passive"))
      (node (ref "FB9") (pin "2") (pinfunction "2_2") (pintype "passive"))
    )
    (net (code "7") (name "SW_DVDDL") (class "Default")
      (node (ref "C137") (pin "1") (pinfunction "1_1") (pintype "passive"))
      (node (ref "C138") (pin "2") (pinfunction "2_2") (pintype "passive"))
      (node (ref "C139") (pin "1") (pinfunction "1_1") (pintype "passive"))
      (node (ref "C140") (pin "1") (pinfunction "1_1") (pintype "passive"))
      (node (ref "C141") (pin "1") (pinfunction "1_1") (pintype "passive"))
      (node (ref "C142") (pin "1") (pinfunction "1_1") (pintype "passive"))
      (node (ref "C143") (pin "1") (pinfunction "1_1") (pintype "passive"))
      (node (ref "C144") (pin "1") (pinfunction "1_1") (pintype "passive"))
      (node (ref "C145") (pin "1") (pinfunction "1_1") (pintype "passive"))
      (node (ref "C146") (pin "1") (pinfunction "1_1") (pintype "passive"))
      (node (ref "C147") (pin "1") (pinfunction "1_1") (pintype "passive"))
      (node (ref "C148") (pin "1") (pinfunction "1_1") (pintype "passive"))
      (node (ref "C178") (pin "2") (pinfunction "2_2") (pintype "passive"))
      (node (ref "R93") (pin "2") (pinfunction "2_2") (pintype "passive"))
    )
    (net (code "8") (name "SW_VDDHS") (class "Default")
      (node (ref "C152") (pin "1") (pinfunction "1_1") (pintype "passive"))
      (node (ref "C153") (pin "2") (pinfunction "2_2") (pintype "passive"))
      (node (ref "C154") (pin "1") (pinfunction "1_1") (pintype "passive"))
      (node (ref "C155") (pin "1") (pinfunction "1_1") (pintype "passive"))
      (node (ref "C156") (pin "1") (pinfunction "1_1") (pintype "passive"))
      (node (ref "C179") (pin "2") (pinfunction "2_2") (pintype "passive"))
      (node (ref "FB10") (pin "2") (pinfunction "2_2") (pintype "passive"))
    )
    (net (code "9") (name "SW_VDDIO") (class "Default")
      (node (ref "C168") (pin "1") (pinfunction "1_1") (pintype "passive"))
      (node (ref "C169") (pin "2") (pinfunction "2_2") (pintype "passive"))
      (node (ref "C170") (pin "1") (pinfunction "1_1") (pintype "passive"))
      (node (ref "C171") (pin "1") (pinfunction "1_1") (pintype "passive"))
      (node (ref "C172") (pin "1") (pinfunction "1_1") (pintype "passive"))
      (node (ref "C173") (pin "1") (pinfunction "1_1") (pintype "passive"))
      (node (ref "C181") (pin "2") (pinfunction "2_2") (pintype "passive"))
      (node (ref "R94") (pin "2") (pinfunction "2_2") (pintype "passive"))
    )
    (net (code "10") (name "SW_VDDLS") (class "Default")
      (node (ref "C160") (pin "1") (pinfunction "1_1") (pintype "passive"))
      (node (ref "C161") (pin "2") (pinfunction "2_2") (pintype "passive"))
      (node (ref "C162") (pin "1") (pinfunction "1_1") (pintype "passive"))
      (node (ref "C163") (pin "1") (pinfunction "1_1") (pintype "passive"))
      (node (ref "C164") (pin "1") (pinfunction "1_1") (pintype "passive"))
      (node (ref "C180") (pin "2") (pinfunction "2_2") (pintype "passive"))
      (node (ref "FB11") (pin "2") (pinfunction "2_2") (pintype "passive"))
    )
  )
)
